# WEN_LM27762.net
KiCad netlist of a schematic drawn in EasyEDA Pro
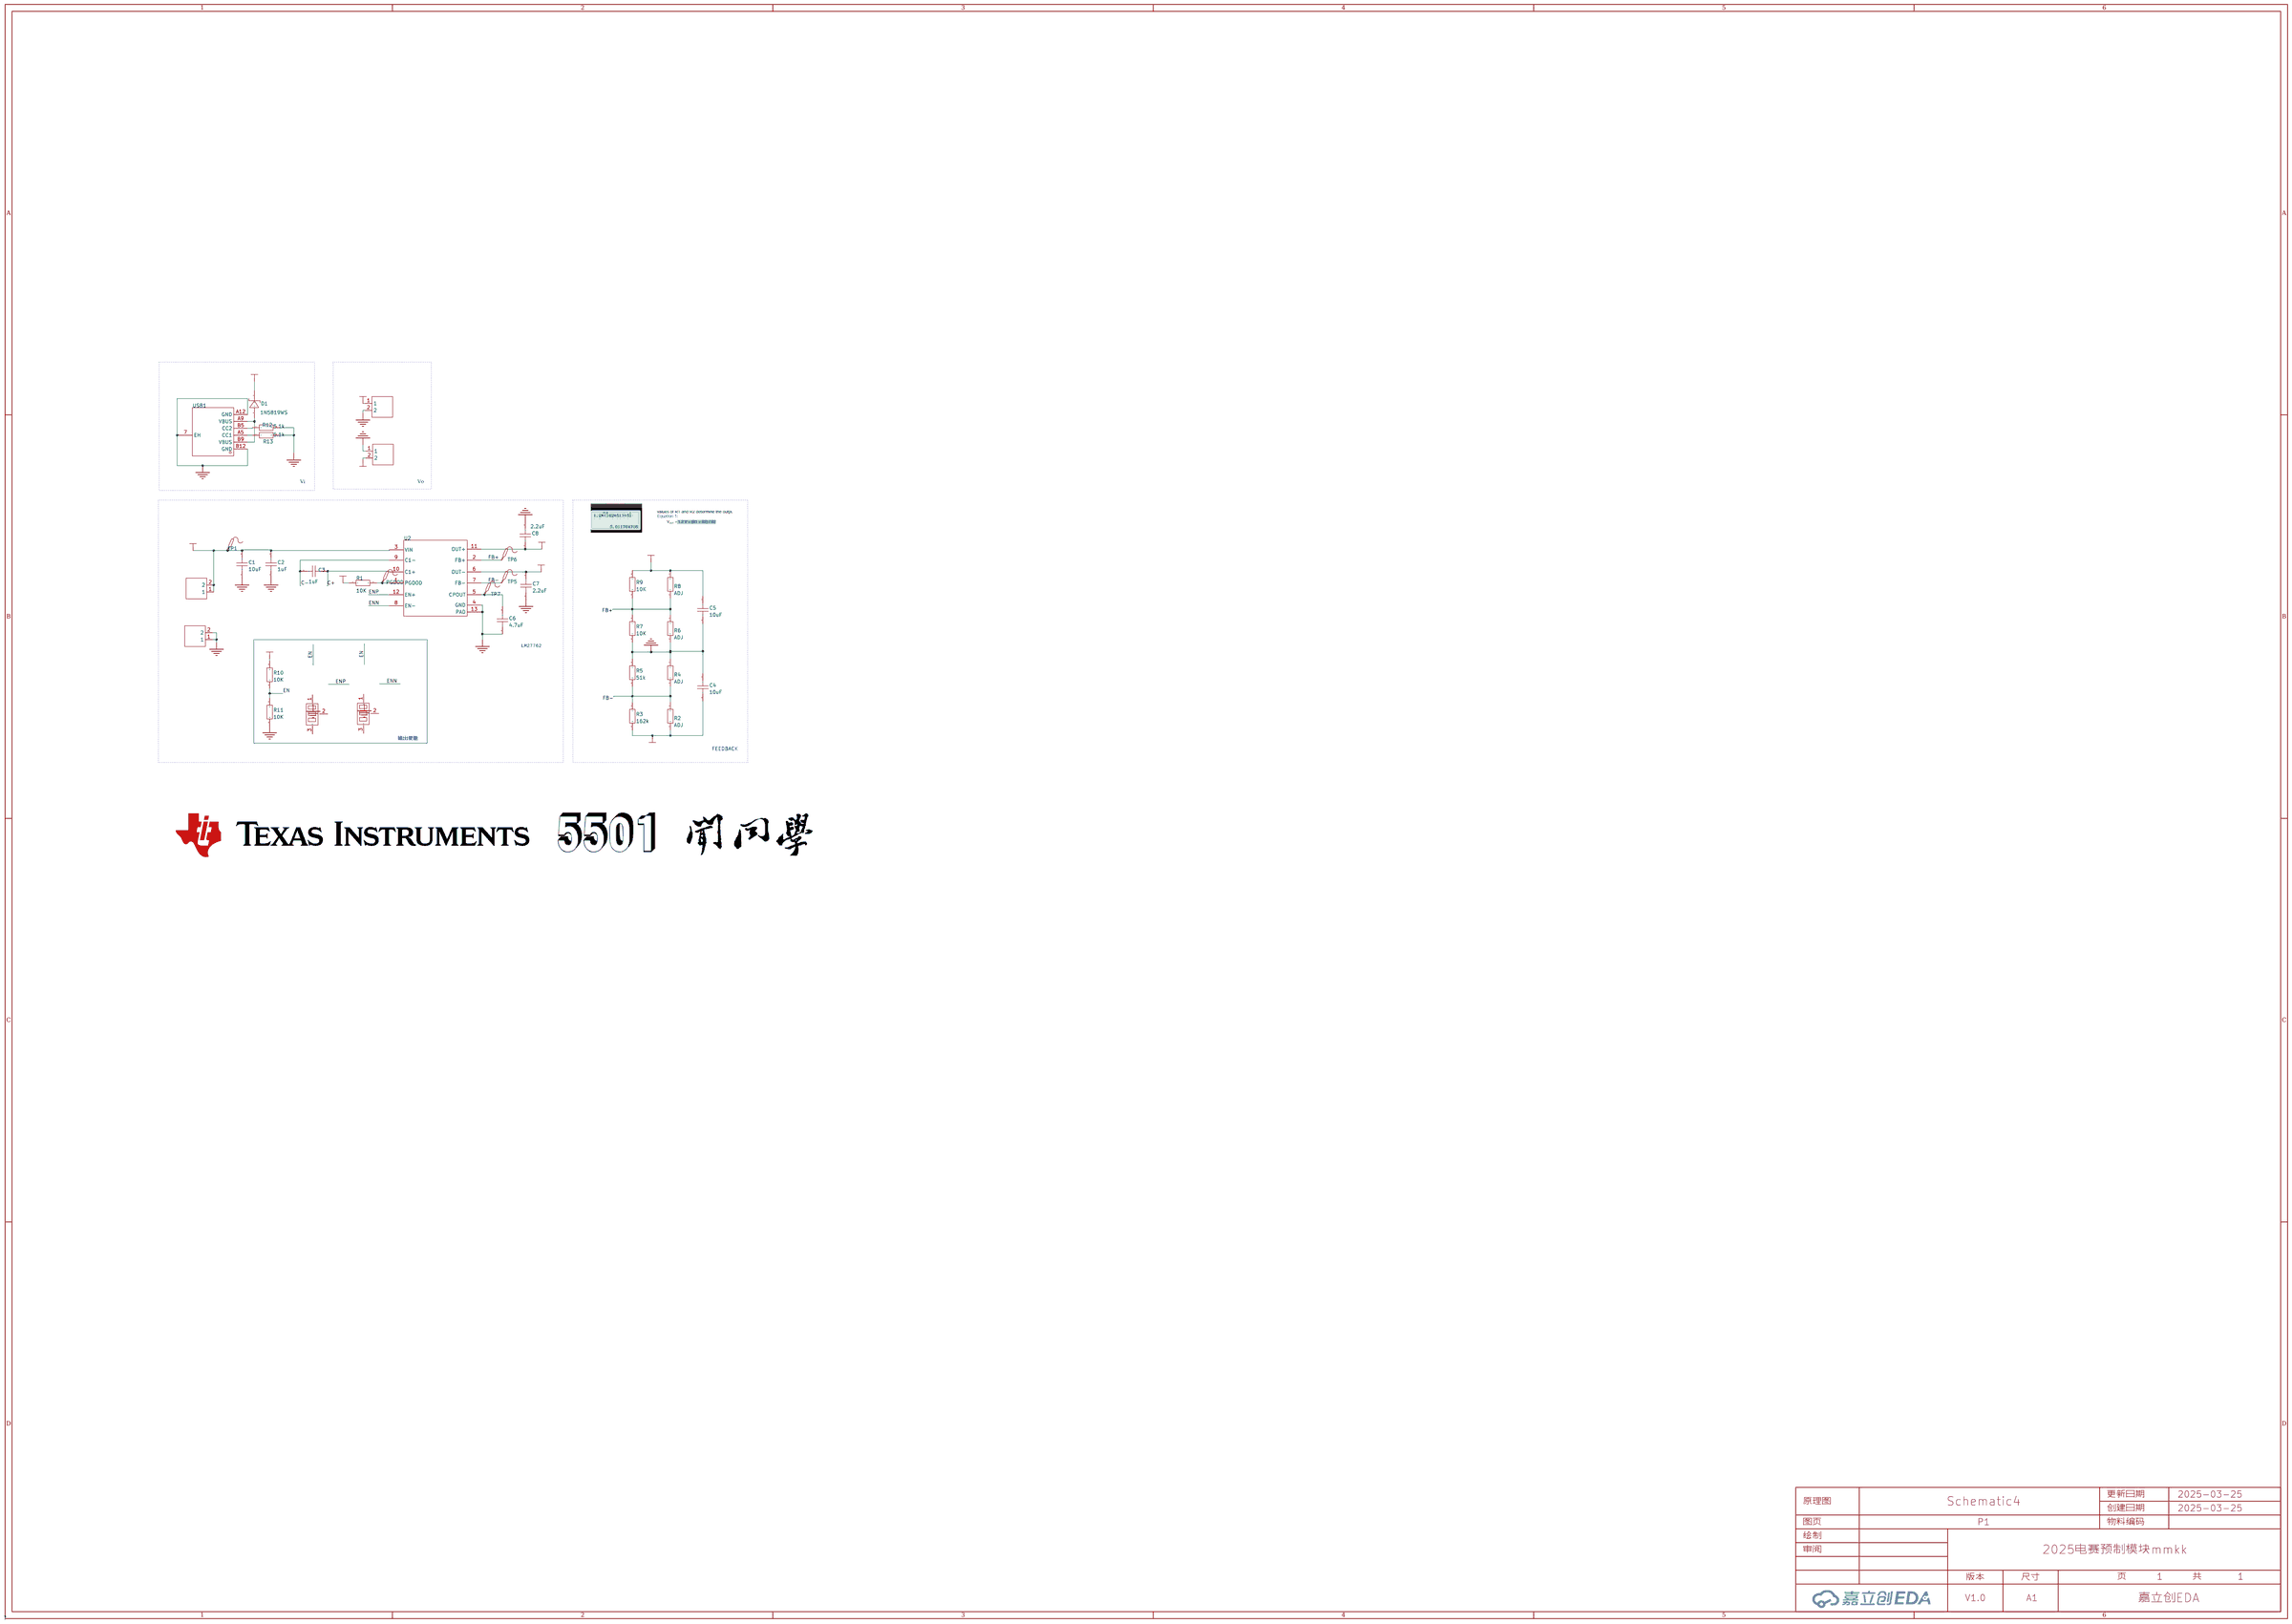
[diagram p0: schematic sheet]

(export (version "E")
  (design (tool "Eeschema 10.0.6"))
  (components
    (comp (ref "C1")
      (value "10uF")
      (footprint "easyedapro:C0603")
      (description "容值:10uF;精度:±10%;额定电压:10V;温度系数:X5R;")
      (fields
        (field (name "Manufacturer Part") "CGA0603X5R106K100JT")
        (field (name "Manufacturer") "HRE(芯声)")
      )
      (libsource (lib "easyedapro") (part "CGA0603X5R106K100JT"))
    )
    (comp (ref "C2")
      (value "1uF")
      (footprint "easyedapro:C0603")
      (description "容值:10uF;精度:±10%;额定电压:10V;温度系数:X5R;")
      (fields
        (field (name "Manufacturer Part") "CGA0603X5R106K100JT")
        (field (name "Manufacturer") "HRE(芯声)")
      )
      (libsource (lib "easyedapro") (part "CGA0603X5R106K100JT"))
    )
    (comp (ref "C3")
      (value "1uF")
      (footprint "easyedapro:C0603")
      (description "容值:10uF;精度:±10%;额定电压:10V;温度系数:X5R;")
      (fields
        (field (name "Manufacturer Part") "CGA0603X5R106K100JT")
        (field (name "Manufacturer") "HRE(芯声)")
      )
      (libsource (lib "easyedapro") (part "CGA0603X5R106K100JT"))
    )
    (comp (ref "C4")
      (value "10uF")
      (footprint "easyedapro:C0603")
      (description "容值:10uF;精度:±10%;额定电压:10V;温度系数:X5R;")
      (fields
        (field (name "Manufacturer Part") "CGA0603X5R106K100JT")
        (field (name "Manufacturer") "HRE(芯声)")
      )
      (libsource (lib "easyedapro") (part "CGA0603X5R106K100JT"))
    )
    (comp (ref "C5")
      (value "10uF")
      (footprint "easyedapro:C0603")
      (description "容值:10uF;精度:±10%;额定电压:10V;温度系数:X5R;")
      (fields
        (field (name "Manufacturer Part") "CGA0603X5R106K100JT")
        (field (name "Manufacturer") "HRE(芯声)")
      )
      (libsource (lib "easyedapro") (part "CGA0603X5R106K100JT"))
    )
    (comp (ref "C6")
      (value "4.7uF")
      (footprint "easyedapro:C0603")
      (description "容值:10uF;精度:±10%;额定电压:10V;温度系数:X5R;")
      (fields
        (field (name "Manufacturer Part") "CGA0603X5R106K100JT")
        (field (name "Manufacturer") "HRE(芯声)")
      )
      (libsource (lib "easyedapro") (part "CGA0603X5R106K100JT"))
    )
    (comp (ref "C7")
      (value "2.2uF")
      (footprint "easyedapro:C0603")
      (description "容值:10uF;精度:±10%;额定电压:10V;温度系数:X5R;")
      (fields
        (field (name "Manufacturer Part") "CGA0603X5R106K100JT")
        (field (name "Manufacturer") "HRE(芯声)")
      )
      (libsource (lib "easyedapro") (part "CGA0603X5R106K100JT"))
    )
    (comp (ref "C8")
      (value "2.2uF")
      (footprint "easyedapro:C0603")
      (description "容值:10uF;精度:±10%;额定电压:10V;温度系数:X5R;")
      (fields
        (field (name "Manufacturer Part") "CGA0603X5R106K100JT")
        (field (name "Manufacturer") "HRE(芯声)")
      )
      (libsource (lib "easyedapro") (part "CGA0603X5R106K100JT"))
    )
    (comp (ref "D1")
      (value "1N5819WS")
      (footprint "easyedapro:SOD-323_L1.8-W1.3-LS2.5-RD")
      (description "直流反向耐压(Vr):40V;平均整流电流(Io):1A;正向压降(Vf):600mV@1A;")
      (fields (field (name "Manufacturer") "Hottech(合科泰)"))
      (libsource (lib "easyedapro") (part "1N5819WS"))
    )
    (comp (ref "H1")
      (value "B-2100S02P-A110")
      (footprint "easyedapro:HDR-TH_2P-P2.54-V-M-1")
      (fields (field (name "Manufacturer") "Ckmtw(灿科盟)"))
      (libsource (lib "easyedapro") (part "210S-1*2P L=11.6MMGold-plated black"))
    )
    (comp (ref "H2")
      (value "B-2100S02P-A110")
      (footprint "easyedapro:HDR-TH_2P-P2.54-V-M-1")
      (fields (field (name "Manufacturer") "Ckmtw(灿科盟)"))
      (libsource (lib "easyedapro") (part "210S-1*2P L=11.6MMGold-plated black"))
    )
    (comp (ref "H3")
      (value "B-2100S02P-A110")
      (footprint "easyedapro:HDR-TH_2P-P2.54-V-M-1")
      (fields (field (name "Manufacturer") "Ckmtw(灿科盟)"))
      (libsource (lib "easyedapro") (part "210S-1*2P L=11.6MMGold-plated black"))
    )
    (comp (ref "H4")
      (value "B-2100S02P-A110")
      (footprint "easyedapro:HDR-TH_2P-P2.54-V-M-1")
      (fields (field (name "Manufacturer") "Ckmtw(灿科盟)"))
      (libsource (lib "easyedapro") (part "210S-1*2P L=11.6MMGold-plated black"))
    )
    (comp (ref "PGOOD")
      (value "~")
      (footprint "easyedapro:Test-Point-0.5mm")
      (description "Test Point 测试点")
      (libsource (lib "easyedapro") (part "Test-Point"))
    )
    (comp (ref "R1")
      (value "10K")
      (footprint "easyedapro:R0603")
      (libsource (lib "easyedapro") (part "0603电阻"))
    )
    (comp (ref "R2")
      (value "ADJ")
      (footprint "easyedapro:R0603")
      (libsource (lib "easyedapro") (part "0603电阻"))
    )
    (comp (ref "R3")
      (value "162k")
      (footprint "easyedapro:R0603")
      (libsource (lib "easyedapro") (part "0603电阻"))
    )
    (comp (ref "R4")
      (value "ADJ")
      (footprint "easyedapro:R0603")
      (libsource (lib "easyedapro") (part "0603电阻"))
    )
    (comp (ref "R5")
      (value "51k")
      (footprint "easyedapro:R0603")
      (libsource (lib "easyedapro") (part "0603电阻"))
    )
    (comp (ref "R6")
      (value "ADJ")
      (footprint "easyedapro:R0603")
      (libsource (lib "easyedapro") (part "0603电阻"))
    )
    (comp (ref "R7")
      (value "10K")
      (footprint "easyedapro:R0603")
      (libsource (lib "easyedapro") (part "0603电阻"))
    )
    (comp (ref "R8")
      (value "ADJ")
      (footprint "easyedapro:R0603")
      (libsource (lib "easyedapro") (part "0603电阻"))
    )
    (comp (ref "R9")
      (value "10K")
      (footprint "easyedapro:R0603")
      (libsource (lib "easyedapro") (part "0603电阻"))
    )
    (comp (ref "R10")
      (value "10K")
      (footprint "easyedapro:R0603")
      (libsource (lib "easyedapro") (part "0603电阻"))
    )
    (comp (ref "R11")
      (value "10K")
      (footprint "easyedapro:R0603")
      (libsource (lib "easyedapro") (part "0603电阻"))
    )
    (comp (ref "R12")
      (value "5.1k")
      (footprint "easyedapro:R0603")
      (libsource (lib "easyedapro") (part "0603电阻"))
    )
    (comp (ref "R13")
      (value "5.1k")
      (footprint "easyedapro:R0603")
      (libsource (lib "easyedapro") (part "0603电阻"))
    )
    (comp (ref "TP1")
      (value "~")
      (footprint "easyedapro:Test-Point-0.5mm")
      (description "Test Point 测试点")
      (libsource (lib "easyedapro") (part "Test-Point"))
    )
    (comp (ref "TP5")
      (value "~")
      (footprint "easyedapro:Test-Point-0.5mm")
      (description "Test Point 测试点")
      (libsource (lib "easyedapro") (part "Test-Point"))
    )
    (comp (ref "TP6")
      (value "~")
      (footprint "easyedapro:Test-Point-0.5mm")
      (description "Test Point 测试点")
      (libsource (lib "easyedapro") (part "Test-Point"))
    )
    (comp (ref "TP7")
      (value "~")
      (footprint "easyedapro:Test-Point-0.5mm")
      (description "Test Point 测试点")
      (libsource (lib "easyedapro") (part "Test-Point"))
    )
    (comp (ref "U2")
      (value "~")
      (footprint "easyedapro:WSON-12_L3.0-W2.0-P0.50-BL-EP-1")
      (libsource (lib "easyedapro") (part "LM27762DSSR"))
    )
    (comp (ref "U3")
      (value "~")
      (footprint "easyedapro:切换短接焊盘")
      (libsource (lib "easyedapro") (part "3P切换短接焊盘"))
    )
    (comp (ref "U4")
      (value "~")
      (footprint "easyedapro:切换短接焊盘")
      (libsource (lib "easyedapro") (part "3P切换短接焊盘"))
    )
    (comp (ref "USB1")
      (value "TYPE-C 6P(073)")
      (footprint "easyedapro:TYPE-C-SMD_TYPE-C-6P_5")
      (description "连接器类型:Type-C;标准:USB 3.1;公母:母;安装方式:卧贴;触点数量:6P;端口数量:1;额定电流 - 电源:3A;工作温度范围:-25°C~+85°C;")
      (fields (field (name "Manufacturer") "SHOU HAN(首韩)"))
      (libsource (lib "easyedapro") (part "TYPE-C 6P(073)"))
    )
  )
  (nets
    (net (code "1") (name "+5V") (class "Default")
      (node (ref "C5") (pin "1") (pinfunction "1_1") (pintype "unspecified"))
      (node (ref "C8") (pin "1") (pinfunction "1_1") (pintype "unspecified"))
      (node (ref "H2") (pin "1") (pinfunction "1_1") (pintype "unspecified"))
      (node (ref "R8") (pin "1") (pinfunction "1_1") (pintype "input"))
      (node (ref "R9") (pin "1") (pinfunction "1_1") (pintype "input"))
      (node (ref "U2") (pin "11") (pinfunction "OUT+_11") (pintype "input"))
    )
    (net (code "2") (name "-5V") (class "Default")
      (node (ref "C4") (pin "2") (pinfunction "2_2") (pintype "unspecified"))
      (node (ref "C7") (pin "2") (pinfunction "2_2") (pintype "unspecified"))
      (node (ref "H3") (pin "2") (pinfunction "2_2") (pintype "unspecified"))
      (node (ref "R2") (pin "2") (pinfunction "2_2") (pintype "input"))
      (node (ref "R3") (pin "2") (pinfunction "2_2") (pintype "input"))
      (node (ref "U2") (pin "6") (pinfunction "OUT-_6") (pintype "input"))
    )
    (net (code "3") (name "/C+") (class "Default")
      (node (ref "C3") (pin "1") (pinfunction "1_1") (pintype "unspecified"))
      (node (ref "U2") (pin "10") (pinfunction "C1+_10") (pintype "input"))
    )
    (net (code "4") (name "/C-") (class "Default")
      (node (ref "C3") (pin "2") (pinfunction "2_2") (pintype "unspecified"))
      (node (ref "U2") (pin "9") (pinfunction "C1-_9") (pintype "input"))
    )
    (net (code "5") (name "/EN") (class "Default")
      (node (ref "R10") (pin "1") (pinfunction "1_1") (pintype "input"))
      (node (ref "R11") (pin "2") (pinfunction "2_2") (pintype "input"))
    )
    (net (code "6") (name "/ENN") (class "Default")
      (node (ref "U2") (pin "8") (pinfunction "EN-_8") (pintype "input"))
    )
    (net (code "7") (name "/ENP") (class "Default")
      (node (ref "U2") (pin "12") (pinfunction "EN+_12") (pintype "input"))
    )
    (net (code "8") (name "/FB+") (class "Default")
      (node (ref "R6") (pin "1") (pinfunction "1_1") (pintype "input"))
      (node (ref "R7") (pin "1") (pinfunction "1_1") (pintype "input"))
      (node (ref "R8") (pin "2") (pinfunction "2_2") (pintype "input"))
      (node (ref "R9") (pin "2") (pinfunction "2_2") (pintype "input"))
      (node (ref "TP6") (pin "1") (pinfunction "1_1") (pintype "input"))
      (node (ref "U2") (pin "2") (pinfunction "FB+_2") (pintype "input"))
    )
    (net (code "9") (name "/FB-") (class "Default")
      (node (ref "R2") (pin "1") (pinfunction "1_1") (pintype "input"))
      (node (ref "R3") (pin "1") (pinfunction "1_1") (pintype "input"))
      (node (ref "R4") (pin "2") (pinfunction "2_2") (pintype "input"))
      (node (ref "R5") (pin "2") (pinfunction "2_2") (pintype "input"))
      (node (ref "TP5") (pin "1") (pinfunction "1_1") (pintype "input"))
      (node (ref "U2") (pin "7") (pinfunction "FB-_7") (pintype "input"))
    )
    (net (code "10") (name "GND") (class "Default")
      (node (ref "C1") (pin "1") (pinfunction "1_1") (pintype "unspecified"))
      (node (ref "C2") (pin "1") (pinfunction "1_1") (pintype "unspecified"))
      (node (ref "C4") (pin "1") (pinfunction "1_1") (pintype "unspecified"))
      (node (ref "C5") (pin "2") (pinfunction "2_2") (pintype "unspecified"))
      (node (ref "C6") (pin "1") (pinfunction "1_1") (pintype "unspecified"))
      (node (ref "C7") (pin "1") (pinfunction "1_1") (pintype "unspecified"))
      (node (ref "C8") (pin "2") (pinfunction "2_2") (pintype "unspecified"))
      (node (ref "H2") (pin "2") (pinfunction "2_2") (pintype "unspecified"))
      (node (ref "H3") (pin "1") (pinfunction "1_1") (pintype "unspecified"))
      (node (ref "H4") (pin "1") (pinfunction "1_1") (pintype "unspecified"))
      (node (ref "H4") (pin "2") (pinfunction "2_2") (pintype "unspecified"))
      (node (ref "R11") (pin "1") (pinfunction "1_1") (pintype "input"))
      (node (ref "R12") (pin "2") (pinfunction "2_2") (pintype "input"))
      (node (ref "R13") (pin "2") (pinfunction "2_2") (pintype "input"))
      (node (ref "R4") (pin "1") (pinfunction "1_1") (pintype "input"))
      (node (ref "R5") (pin "1") (pinfunction "1_1") (pintype "input"))
      (node (ref "R6") (pin "2") (pinfunction "2_2") (pintype "input"))
      (node (ref "R7") (pin "2") (pinfunction "2_2") (pintype "input"))
      (node (ref "U2") (pin "13") (pinfunction "PAD_13") (pintype "input"))
      (node (ref "U2") (pin "4") (pinfunction "GND_4") (pintype "input"))
      (node (ref "USB1") (pin "7") (pinfunction "EH_7") (pintype "unspecified"))
      (node (ref "USB1") (pin "A12") (pinfunction "GND_A12") (pintype "unspecified"))
      (node (ref "USB1") (pin "B12") (pinfunction "GND_B12") (pintype "unspecified"))
    )
    (net (code "11") (name "Net-(D1-A)") (class "Default")
      (node (ref "D1") (pin "2") (pinfunction "A_2") (pintype "input"))
      (node (ref "USB1") (pin "A9") (pinfunction "VBUS_A9") (pintype "unspecified"))
      (node (ref "USB1") (pin "B9") (pinfunction "VBUS_B9") (pintype "unspecified"))
    )
    (net (code "12") (name "Net-(U2-CPOUT)") (class "Default")
      (node (ref "C6") (pin "2") (pinfunction "2_2") (pintype "unspecified"))
      (node (ref "TP7") (pin "1") (pinfunction "1_1") (pintype "input"))
      (node (ref "U2") (pin "5") (pinfunction "CPOUT_5") (pintype "input"))
    )
    (net (code "13") (name "Net-(U2-PGOOD)") (class "Default")
      (node (ref "PGOOD") (pin "1") (pinfunction "1_1") (pintype "input"))
      (node (ref "R1") (pin "2") (pinfunction "2_2") (pintype "input"))
      (node (ref "U2") (pin "1") (pinfunction "PGOOD_1") (pintype "input"))
    )
    (net (code "14") (name "Net-(USB1-CC1)") (class "Default")
      (node (ref "R13") (pin "1") (pinfunction "1_1") (pintype "input"))
      (node (ref "USB1") (pin "A5") (pinfunction "CC1_A5") (pintype "unspecified"))
    )
    (net (code "15") (name "Net-(USB1-CC2)") (class "Default")
      (node (ref "R12") (pin "1") (pinfunction "1_1") (pintype "input"))
      (node (ref "USB1") (pin "B5") (pinfunction "CC2_B5") (pintype "unspecified"))
    )
    (net (code "16") (name "VIN") (class "Default")
      (node (ref "C1") (pin "2") (pinfunction "2_2") (pintype "unspecified"))
      (node (ref "C2") (pin "2") (pinfunction "2_2") (pintype "unspecified"))
      (node (ref "D1") (pin "1") (pinfunction "C_1") (pintype "input"))
      (node (ref "H1") (pin "1") (pinfunction "1_1") (pintype "unspecified"))
      (node (ref "H1") (pin "2") (pinfunction "2_2") (pintype "unspecified"))
      (node (ref "R1") (pin "1") (pinfunction "1_1") (pintype "input"))
      (node (ref "R10") (pin "2") (pinfunction "2_2") (pintype "input"))
      (node (ref "TP1") (pin "1") (pinfunction "1_1") (pintype "input"))
      (node (ref "U2") (pin "3") (pinfunction "VIN_3") (pintype "input"))
    )
    (net (code "17") (name "unconnected-(U3-Pad1)") (class "Default")
      (node (ref "U3") (pin "1") (pinfunction "1_1") (pintype "input"))
    )
    (net (code "18") (name "unconnected-(U3-Pad2)") (class "Default")
      (node (ref "U3") (pin "2") (pinfunction "2_2") (pintype "input"))
    )
    (net (code "19") (name "unconnected-(U3-Pad3)") (class "Default")
      (node (ref "U3") (pin "3") (pinfunction "3_3") (pintype "input"))
    )
    (net (code "20") (name "unconnected-(U4-Pad1)") (class "Default")
      (node (ref "U4") (pin "1") (pinfunction "1_1") (pintype "input"))
    )
    (net (code "21") (name "unconnected-(U4-Pad2)") (class "Default")
      (node (ref "U4") (pin "2") (pinfunction "2_2") (pintype "input"))
    )
    (net (code "22") (name "unconnected-(U4-Pad3)") (class "Default")
      (node (ref "U4") (pin "3") (pinfunction "3_3") (pintype "input"))
    )
  )
)
